# FitzSPA10.net
KiCad netlist of a schematic drawn in EAGLE
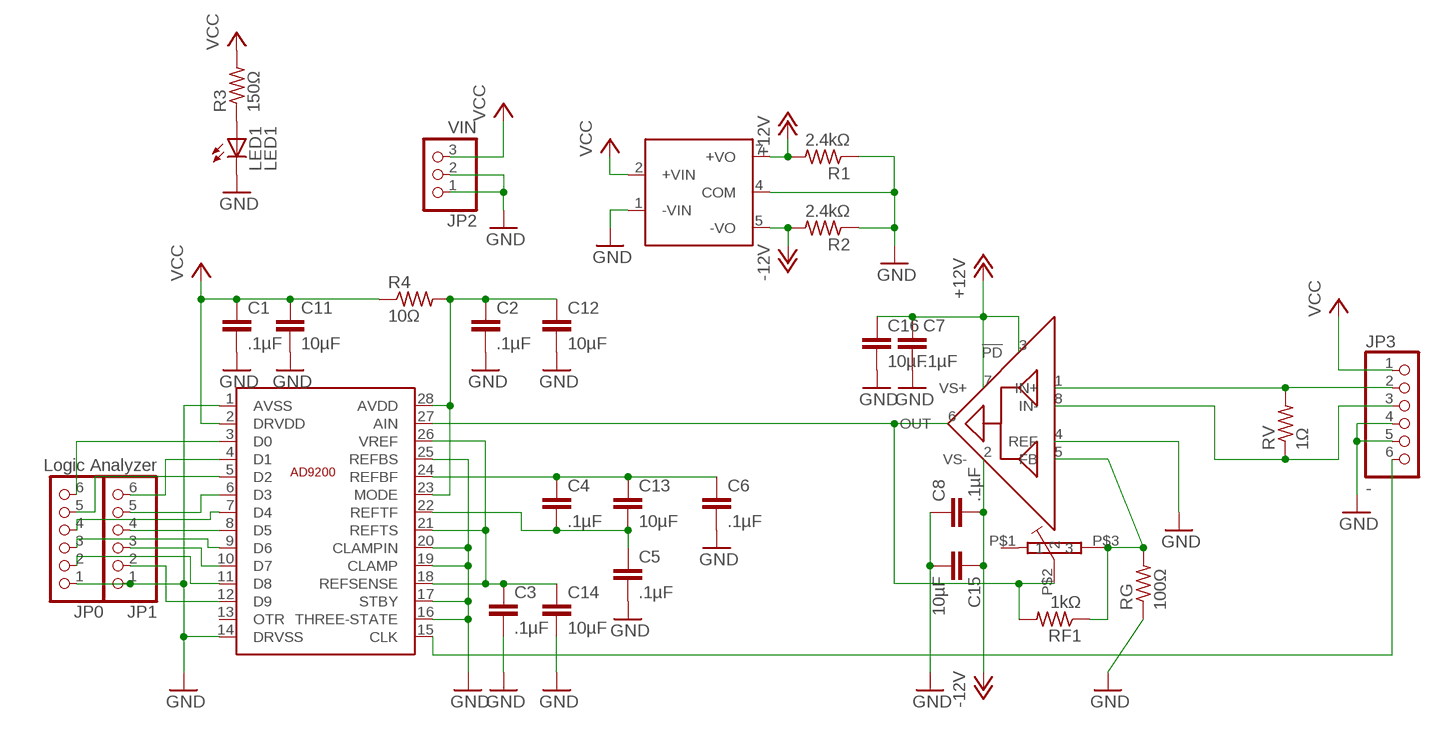
[diagram p0: schematic, sheet 1]

(export (version "E")
  (design (tool "Eeschema 10.0.6"))
  (components
    (comp (ref "C1")
      (value ".1µF")
      (footprint "eagle-import:C0603")
      (libsource (lib "eagle-import") (part "C-EUC0603"))
    )
    (comp (ref "C2")
      (value ".1µF")
      (footprint "eagle-import:C0603")
      (libsource (lib "eagle-import") (part "C-EUC0603"))
    )
    (comp (ref "C3")
      (value ".1µF")
      (footprint "eagle-import:C0603")
      (libsource (lib "eagle-import") (part "C-EUC0603"))
    )
    (comp (ref "C4")
      (value ".1µF")
      (footprint "eagle-import:C0603")
      (libsource (lib "eagle-import") (part "C-EUC0603"))
    )
    (comp (ref "C5")
      (value ".1µF")
      (footprint "eagle-import:C0603")
      (libsource (lib "eagle-import") (part "C-EUC0603"))
    )
    (comp (ref "C6")
      (value ".1µF")
      (footprint "eagle-import:C0603")
      (libsource (lib "eagle-import") (part "C-EUC0603"))
    )
    (comp (ref "C7")
      (value ".1µF")
      (footprint "eagle-import:C0603")
      (libsource (lib "eagle-import") (part "C-EUC0603"))
    )
    (comp (ref "C8")
      (value ".1µF")
      (footprint "eagle-import:C0603")
      (libsource (lib "eagle-import") (part "C-EUC0603"))
    )
    (comp (ref "C11")
      (value "10µF")
      (footprint "eagle-import:C0805")
      (libsource (lib "eagle-import") (part "C-EUC0805"))
    )
    (comp (ref "C12")
      (value "10µF")
      (footprint "eagle-import:C0805")
      (libsource (lib "eagle-import") (part "C-EUC0805"))
    )
    (comp (ref "C13")
      (value "10µF")
      (footprint "eagle-import:C0805")
      (libsource (lib "eagle-import") (part "C-EUC0805"))
    )
    (comp (ref "C14")
      (value "10µF")
      (footprint "eagle-import:C0805")
      (libsource (lib "eagle-import") (part "C-EUC0805"))
    )
    (comp (ref "C15")
      (value "10µF")
      (footprint "eagle-import:C0805")
      (libsource (lib "eagle-import") (part "C-EUC0805"))
    )
    (comp (ref "C16")
      (value "10µF")
      (footprint "eagle-import:C0805")
      (libsource (lib "eagle-import") (part "C-EUC0805"))
    )
    (comp (ref "JP0")
      (value "PINHD-1X6LOCK")
      (footprint "eagle-import:1X06-BIGLOCK")
      (libsource (lib "eagle-import") (part "PINHD-1X6LOCK"))
    )
    (comp (ref "JP1")
      (value "Logic Analyzer")
      (footprint "eagle-import:1X06-BIGLOCK")
      (libsource (lib "eagle-import") (part "PINHD-1X6LOCK"))
    )
    (comp (ref "JP2")
      (value "VIN")
      (footprint "eagle-import:1X03")
      (libsource (lib "eagle-import") (part "PINHD-1X3"))
    )
    (comp (ref "JP3")
      (value "-")
      (footprint "eagle-import:1X06-BIGLOCK")
      (libsource (lib "eagle-import") (part "PINHD-1X6LOCK"))
    )
    (comp (ref "LED1")
      (value "LED1")
      (footprint "eagle-import:CHIPLED_0603")
      (libsource (lib "eagle-import") (part "LEDCHIPLED_0603"))
    )
    (comp (ref "R1")
      (value "2.4kΩ")
      (footprint "eagle-import:R0603")
      (libsource (lib "eagle-import") (part "R-US_R0603"))
    )
    (comp (ref "R2")
      (value "2.4kΩ")
      (footprint "eagle-import:R0603")
      (libsource (lib "eagle-import") (part "R-US_R0603"))
    )
    (comp (ref "R3")
      (value "150Ω")
      (footprint "eagle-import:R0603")
      (libsource (lib "eagle-import") (part "R-US_R0603"))
    )
    (comp (ref "R4")
      (value "10Ω")
      (footprint "eagle-import:R0603")
      (libsource (lib "eagle-import") (part "R-US_R0603"))
    )
    (comp (ref "RF")
      (value "10kΩ")
      (footprint "eagle-import:MODEL84POT")
      (libsource (lib "eagle-import") (part "MODEL84POT"))
    )
    (comp (ref "RF1")
      (value "1kΩ")
      (footprint "eagle-import:R0603")
      (libsource (lib "eagle-import") (part "R-US_R0603"))
    )
    (comp (ref "RG")
      (value "100Ω")
      (footprint "eagle-import:R0603")
      (libsource (lib "eagle-import") (part "R-US_R0603"))
    )
    (comp (ref "RV")
      (value "1Ω")
      (footprint "eagle-import:R0603")
      (libsource (lib "eagle-import") (part "R-US_R0603"))
    )
    (comp (ref "U1")
      (value "AD9200ARZ")
      (footprint "eagle-import:SSOP28")
      (libsource (lib "eagle-import") (part "AD9200ARZ"))
    )
    (comp (ref "U2")
      (value "AD8129ARMZ")
      (footprint "eagle-import:MSOP8")
      (libsource (lib "eagle-import") (part "AD8129ARMZ"))
    )
    (comp (ref "U3")
      (value "VAT1-SMT")
      (footprint "eagle-import:VAT1-SMT")
      (libsource (lib "eagle-import") (part "VAT1-SMT"))
    )
  )
  (nets
    (net (code "1") (name "+12V") (class "Default")
      (node (ref "C16") (pin "1") (pinfunction "1_1") (pintype "passive"))
      (node (ref "C7") (pin "1") (pinfunction "1_1") (pintype "passive"))
      (node (ref "R1") (pin "2") (pinfunction "2_2") (pintype "passive"))
      (node (ref "U2") (pin "3") (pinfunction "~{PD}_3") (pintype "bidirectional"))
      (node (ref "U2") (pin "7") (pinfunction "VS+_7") (pintype "bidirectional"))
      (node (ref "U3") (pin "7") (pinfunction "+VO_7") (pintype "bidirectional"))
    )
    (net (code "2") (name "-12V") (class "Default")
      (node (ref "C15") (pin "1") (pinfunction "1_1") (pintype "passive"))
      (node (ref "C8") (pin "2") (pinfunction "2_2") (pintype "passive"))
      (node (ref "R2") (pin "2") (pinfunction "2_2") (pintype "passive"))
      (node (ref "U2") (pin "2") (pinfunction "VS-_2") (pintype "bidirectional"))
      (node (ref "U3") (pin "5") (pinfunction "-VO_5") (pintype "bidirectional"))
    )
    (net (code "3") (name "GND") (class "Default")
      (node (ref "C1") (pin "2") (pinfunction "2_2") (pintype "passive"))
      (node (ref "C11") (pin "2") (pinfunction "2_2") (pintype "passive"))
      (node (ref "C12") (pin "2") (pinfunction "2_2") (pintype "passive"))
      (node (ref "C14") (pin "2") (pinfunction "2_2") (pintype "passive"))
      (node (ref "C15") (pin "2") (pinfunction "2_2") (pintype "passive"))
      (node (ref "C16") (pin "2") (pinfunction "2_2") (pintype "passive"))
      (node (ref "C2") (pin "2") (pinfunction "2_2") (pintype "passive"))
      (node (ref "C3") (pin "2") (pinfunction "2_2") (pintype "passive"))
      (node (ref "C5") (pin "2") (pinfunction "2_2") (pintype "passive"))
      (node (ref "C6") (pin "2") (pinfunction "2_2") (pintype "passive"))
      (node (ref "C7") (pin "2") (pinfunction "2_2") (pintype "passive"))
      (node (ref "C8") (pin "1") (pinfunction "1_1") (pintype "passive"))
      (node (ref "JP0") (pin "1") (pinfunction "1_1") (pintype "passive"))
      (node (ref "JP1") (pin "1") (pinfunction "1_1") (pintype "passive"))
      (node (ref "JP2") (pin "1") (pinfunction "1_1") (pintype "passive"))
      (node (ref "JP2") (pin "2") (pinfunction "2_2") (pintype "passive"))
      (node (ref "JP3") (pin "4") (pinfunction "4_4") (pintype "passive"))
      (node (ref "JP3") (pin "5") (pinfunction "5_5") (pintype "passive"))
      (node (ref "LED1") (pin "C") (pinfunction "C_C") (pintype "passive"))
      (node (ref "R1") (pin "1") (pinfunction "1_1") (pintype "passive"))
      (node (ref "R2") (pin "1") (pinfunction "1_1") (pintype "passive"))
      (node (ref "RG") (pin "1") (pinfunction "1_1") (pintype "passive"))
      (node (ref "U1") (pin "1") (pinfunction "AVSS_1") (pintype "bidirectional"))
      (node (ref "U1") (pin "14") (pinfunction "DRVSS_14") (pintype "bidirectional"))
      (node (ref "U1") (pin "16") (pinfunction "THREE-STATE_16") (pintype "bidirectional"))
      (node (ref "U1") (pin "17") (pinfunction "STBY_17") (pintype "bidirectional"))
      (node (ref "U1") (pin "19") (pinfunction "CLAMP_19") (pintype "bidirectional"))
      (node (ref "U1") (pin "20") (pinfunction "CLAMPIN_20") (pintype "bidirectional"))
      (node (ref "U1") (pin "25") (pinfunction "REFBS_25") (pintype "bidirectional"))
      (node (ref "U2") (pin "4") (pinfunction "REF_4") (pintype "bidirectional"))
      (node (ref "U3") (pin "1") (pinfunction "-VIN_1") (pintype "bidirectional"))
      (node (ref "U3") (pin "4") (pinfunction "COM_4") (pintype "bidirectional"))
    )
    (net (code "4") (name "Net-(LED1-PadA)") (class "Default")
      (node (ref "LED1") (pin "A") (pinfunction "A_A") (pintype "passive"))
      (node (ref "R3") (pin "1") (pinfunction "1_1") (pintype "passive"))
    )
    (net (code "5") (name "Net-(RF-2)") (class "Default")
      (node (ref "RF") (pin "P$2") (pinfunction "2_P$2") (pintype "bidirectional"))
      (node (ref "RF1") (pin "2") (pinfunction "2_2") (pintype "passive"))
      (node (ref "U1") (pin "27") (pinfunction "AIN_27") (pintype "bidirectional"))
      (node (ref "U2") (pin "6") (pinfunction "OUT_6") (pintype "bidirectional"))
    )
    (net (code "6") (name "Net-(RF-3)") (class "Default")
      (node (ref "RF") (pin "P$3") (pinfunction "3_P$3") (pintype "bidirectional"))
      (node (ref "RF1") (pin "1") (pinfunction "1_1") (pintype "passive"))
      (node (ref "RG") (pin "2") (pinfunction "2_2") (pintype "passive"))
      (node (ref "U2") (pin "5") (pinfunction "FB_5") (pintype "bidirectional"))
    )
    (net (code "7") (name "Net-(U1-AVDD)") (class "Default")
      (node (ref "C12") (pin "1") (pinfunction "1_1") (pintype "passive"))
      (node (ref "C2") (pin "1") (pinfunction "1_1") (pintype "passive"))
      (node (ref "R4") (pin "2") (pinfunction "2_2") (pintype "passive"))
      (node (ref "U1") (pin "23") (pinfunction "MODE_23") (pintype "bidirectional"))
      (node (ref "U1") (pin "28") (pinfunction "AVDD_28") (pintype "bidirectional"))
    )
    (net (code "8") (name "Net-(U1-CLK)") (class "Default")
      (node (ref "JP3") (pin "6") (pinfunction "6_6") (pintype "passive"))
      (node (ref "U1") (pin "15") (pinfunction "CLK_15") (pintype "bidirectional"))
    )
    (net (code "9") (name "Net-(U1-D0)") (class "Default")
      (node (ref "JP0") (pin "6") (pinfunction "6_6") (pintype "passive"))
      (node (ref "U1") (pin "3") (pinfunction "D0_3") (pintype "bidirectional"))
    )
    (net (code "10") (name "Net-(U1-D1)") (class "Default")
      (node (ref "JP1") (pin "6") (pinfunction "6_6") (pintype "passive"))
      (node (ref "U1") (pin "4") (pinfunction "D1_4") (pintype "bidirectional"))
    )
    (net (code "11") (name "Net-(U1-D2)") (class "Default")
      (node (ref "JP0") (pin "5") (pinfunction "5_5") (pintype "passive"))
      (node (ref "U1") (pin "5") (pinfunction "D2_5") (pintype "bidirectional"))
    )
    (net (code "12") (name "Net-(U1-D3)") (class "Default")
      (node (ref "JP1") (pin "5") (pinfunction "5_5") (pintype "passive"))
      (node (ref "U1") (pin "6") (pinfunction "D3_6") (pintype "bidirectional"))
    )
    (net (code "13") (name "Net-(U1-D4)") (class "Default")
      (node (ref "JP0") (pin "4") (pinfunction "4_4") (pintype "passive"))
      (node (ref "U1") (pin "7") (pinfunction "D4_7") (pintype "bidirectional"))
    )
    (net (code "14") (name "Net-(U1-D5)") (class "Default")
      (node (ref "JP1") (pin "4") (pinfunction "4_4") (pintype "passive"))
      (node (ref "U1") (pin "8") (pinfunction "D5_8") (pintype "bidirectional"))
    )
    (net (code "15") (name "Net-(U1-D6)") (class "Default")
      (node (ref "JP0") (pin "3") (pinfunction "3_3") (pintype "passive"))
      (node (ref "U1") (pin "9") (pinfunction "D6_9") (pintype "bidirectional"))
    )
    (net (code "16") (name "Net-(U1-D7)") (class "Default")
      (node (ref "JP1") (pin "3") (pinfunction "3_3") (pintype "passive"))
      (node (ref "U1") (pin "10") (pinfunction "D7_10") (pintype "bidirectional"))
    )
    (net (code "17") (name "Net-(U1-D8)") (class "Default")
      (node (ref "JP0") (pin "2") (pinfunction "2_2") (pintype "passive"))
      (node (ref "U1") (pin "11") (pinfunction "D8_11") (pintype "bidirectional"))
    )
    (net (code "18") (name "Net-(U1-D9)") (class "Default")
      (node (ref "JP1") (pin "2") (pinfunction "2_2") (pintype "passive"))
      (node (ref "U1") (pin "12") (pinfunction "D9_12") (pintype "bidirectional"))
    )
    (net (code "19") (name "Net-(U1-REFBF)") (class "Default")
      (node (ref "C13") (pin "1") (pinfunction "1_1") (pintype "passive"))
      (node (ref "C4") (pin "1") (pinfunction "1_1") (pintype "passive"))
      (node (ref "C6") (pin "1") (pinfunction "1_1") (pintype "passive"))
      (node (ref "U1") (pin "24") (pinfunction "REFBF_24") (pintype "bidirectional"))
    )
    (net (code "20") (name "Net-(U1-REFSENSE)") (class "Default")
      (node (ref "C14") (pin "1") (pinfunction "1_1") (pintype "passive"))
      (node (ref "C3") (pin "1") (pinfunction "1_1") (pintype "passive"))
      (node (ref "U1") (pin "18") (pinfunction "REFSENSE_18") (pintype "bidirectional"))
      (node (ref "U1") (pin "21") (pinfunction "REFTS_21") (pintype "bidirectional"))
      (node (ref "U1") (pin "26") (pinfunction "VREF_26") (pintype "bidirectional"))
    )
    (net (code "21") (name "Net-(U1-REFTF)") (class "Default")
      (node (ref "C13") (pin "2") (pinfunction "2_2") (pintype "passive"))
      (node (ref "C4") (pin "2") (pinfunction "2_2") (pintype "passive"))
      (node (ref "C5") (pin "1") (pinfunction "1_1") (pintype "passive"))
      (node (ref "U1") (pin "22") (pinfunction "REFTF_22") (pintype "bidirectional"))
    )
    (net (code "22") (name "Net-(U2-IN+)") (class "Default")
      (node (ref "JP3") (pin "2") (pinfunction "2_2") (pintype "passive"))
      (node (ref "RV") (pin "2") (pinfunction "2_2") (pintype "passive"))
      (node (ref "U2") (pin "1") (pinfunction "IN+_1") (pintype "bidirectional"))
    )
    (net (code "23") (name "Net-(U2-IN-)") (class "Default")
      (node (ref "JP3") (pin "3") (pinfunction "3_3") (pintype "passive"))
      (node (ref "RV") (pin "1") (pinfunction "1_1") (pintype "passive"))
      (node (ref "U2") (pin "8") (pinfunction "IN-_8") (pintype "bidirectional"))
    )
    (net (code "24") (name "VCC") (class "Default")
      (node (ref "C1") (pin "1") (pinfunction "1_1") (pintype "passive"))
      (node (ref "C11") (pin "1") (pinfunction "1_1") (pintype "passive"))
      (node (ref "JP2") (pin "3") (pinfunction "3_3") (pintype "passive"))
      (node (ref "JP3") (pin "1") (pinfunction "1_1") (pintype "passive"))
      (node (ref "R3") (pin "2") (pinfunction "2_2") (pintype "passive"))
      (node (ref "R4") (pin "1") (pinfunction "1_1") (pintype "passive"))
      (node (ref "U1") (pin "2") (pinfunction "DRVDD_2") (pintype "bidirectional"))
      (node (ref "U3") (pin "2") (pinfunction "+VIN_2") (pintype "bidirectional"))
    )
    (net (code "25") (name "unconnected-(RF-1-PadP$1)") (class "Default")
      (node (ref "RF") (pin "P$1") (pinfunction "1_P$1") (pintype "bidirectional"))
    )
    (net (code "26") (name "unconnected-(U1-OTR-Pad13)") (class "Default")
      (node (ref "U1") (pin "13") (pinfunction "OTR_13") (pintype "bidirectional"))
    )
  )
)
